# miniprinter_x_axis.net
KiCad netlist of a schematic drawn in EAGLE
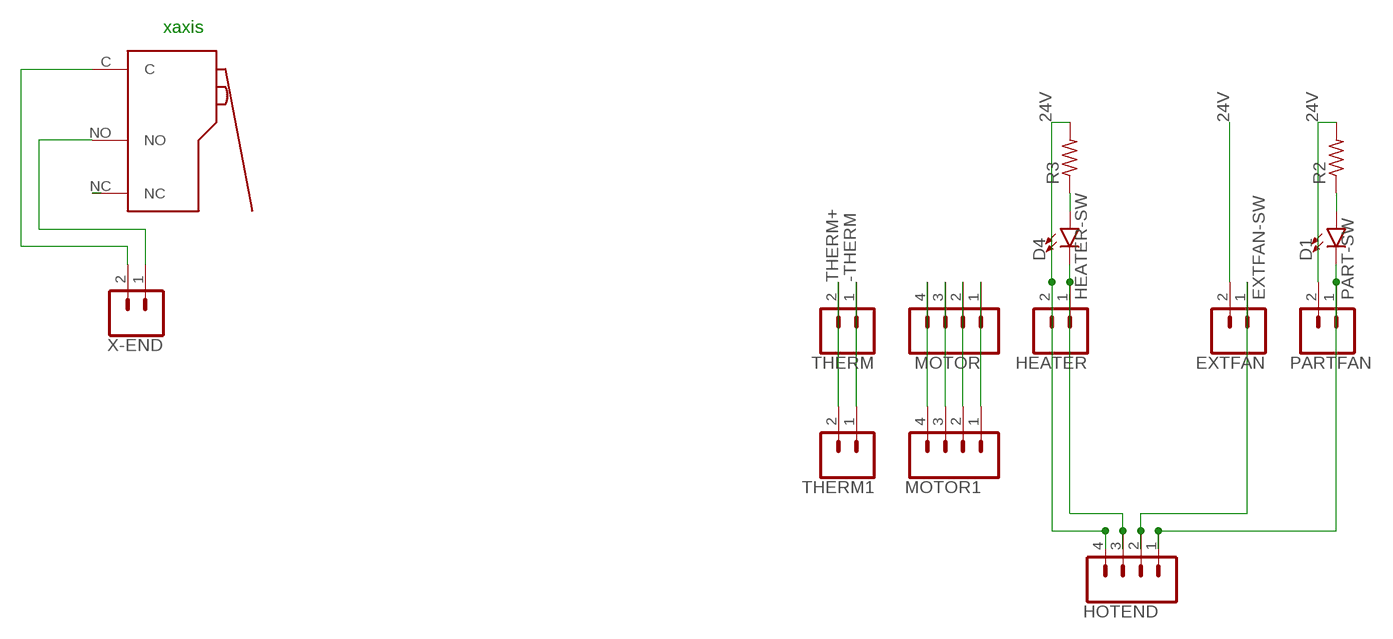
[diagram p0: schematic, sheet 1]

(export (version "E")
  (design (tool "Eeschema 10.0.6"))
  (components
    (comp (ref "D1")
      (value "LED-FKIT-1206")
      (footprint "eagle-import:FKIT-LED-1206")
      (libsource (lib "eagle-import") (part "LED-FKIT-1206"))
    )
    (comp (ref "D4")
      (value "LED-FKIT-1206")
      (footprint "eagle-import:FKIT-LED-1206")
      (libsource (lib "eagle-import") (part "LED-FKIT-1206"))
    )
    (comp (ref "EXTFAN")
      (value "CONN_023.5MM_LOCK")
      (footprint "eagle-import:SCREWTERMINAL-3.5MM-2_LOCK")
      (libsource (lib "eagle-import") (part "CONN_023.5MM_LOCK"))
    )
    (comp (ref "HEATER")
      (value "CONN_023.5MM_LOCK")
      (footprint "eagle-import:SCREWTERMINAL-3.5MM-2_LOCK")
      (libsource (lib "eagle-import") (part "CONN_023.5MM_LOCK"))
    )
    (comp (ref "HOTEND")
      (value "CONN_04SCREW_LOCK")
      (footprint "eagle-import:SCREWTERMINAL-3.5MM-4_LOCK")
      (libsource (lib "eagle-import") (part "CONN_04SCREW_LOCK"))
    )
    (comp (ref "MOTOR")
      (value "CONN_04SCREW_LOCK")
      (footprint "eagle-import:SCREWTERMINAL-3.5MM-4_LOCK")
      (libsource (lib "eagle-import") (part "CONN_04SCREW_LOCK"))
    )
    (comp (ref "MOTOR1")
      (value "CONN_04SCREW_LOCK")
      (footprint "eagle-import:SCREWTERMINAL-3.5MM-4_LOCK")
      (libsource (lib "eagle-import") (part "CONN_04SCREW_LOCK"))
    )
    (comp (ref "PARTFAN")
      (value "CONN_023.5MM_LOCK")
      (footprint "eagle-import:SCREWTERMINAL-3.5MM-2_LOCK")
      (libsource (lib "eagle-import") (part "CONN_023.5MM_LOCK"))
    )
    (comp (ref "R2")
      (value "R-US_R1206")
      (footprint "eagle-import:R1206")
      (libsource (lib "eagle-import") (part "R-US_R1206"))
    )
    (comp (ref "R3")
      (value "R-US_R1206")
      (footprint "eagle-import:R1206")
      (libsource (lib "eagle-import") (part "R-US_R1206"))
    )
    (comp (ref "THERM")
      (value "CONN_023.5MM_LOCK")
      (footprint "eagle-import:SCREWTERMINAL-3.5MM-2_LOCK")
      (libsource (lib "eagle-import") (part "CONN_023.5MM_LOCK"))
    )
    (comp (ref "THERM1")
      (value "CONN_023.5MM_LOCK")
      (footprint "eagle-import:SCREWTERMINAL-3.5MM-2_LOCK")
      (libsource (lib "eagle-import") (part "CONN_023.5MM_LOCK"))
    )
    (comp (ref "U$2")
      (value "Lever Microswitch Leftangle PCB mount, with Roller style lever, with a red roller")
      (footprint "eagle-import:LEVERMICROPCB-LEFTANGLE")
      (libsource (lib "eagle-import") (part "LEVERMICROPCBLEFTANGLE"))
    )
    (comp (ref "X-END")
      (value "CONN_023.5MM_LOCK")
      (footprint "eagle-import:SCREWTERMINAL-3.5MM-2_LOCK")
      (libsource (lib "eagle-import") (part "CONN_023.5MM_LOCK"))
    )
  )
  (nets
    (net (code "1") (name "/-THERM") (class "Default")
      (node (ref "THERM") (pin "1") (pinfunction "1_1") (pintype "passive"))
      (node (ref "THERM1") (pin "1") (pinfunction "1_1") (pintype "passive"))
    )
    (net (code "2") (name "/24V") (class "Default")
      (node (ref "EXTFAN") (pin "2") (pinfunction "2_2") (pintype "passive"))
      (node (ref "HEATER") (pin "2") (pinfunction "2_2") (pintype "passive"))
      (node (ref "HOTEND") (pin "4") (pinfunction "4_4") (pintype "passive"))
      (node (ref "PARTFAN") (pin "2") (pinfunction "2_2") (pintype "passive"))
      (node (ref "R2") (pin "2") (pinfunction "2_2") (pintype "passive"))
      (node (ref "R3") (pin "2") (pinfunction "2_2") (pintype "passive"))
    )
    (net (code "3") (name "/EXTFAN-SW") (class "Default")
      (node (ref "EXTFAN") (pin "1") (pinfunction "1_1") (pintype "passive"))
      (node (ref "HOTEND") (pin "2") (pinfunction "2_2") (pintype "passive"))
    )
    (net (code "4") (name "/HEATER-SW") (class "Default")
      (node (ref "D4") (pin "C") (pinfunction "C_C") (pintype "passive"))
      (node (ref "HEATER") (pin "1") (pinfunction "1_1") (pintype "passive"))
      (node (ref "HOTEND") (pin "3") (pinfunction "3_3") (pintype "passive"))
    )
    (net (code "5") (name "/PART-SW") (class "Default")
      (node (ref "D1") (pin "C") (pinfunction "C_C") (pintype "passive"))
      (node (ref "HOTEND") (pin "1") (pinfunction "1_1") (pintype "passive"))
      (node (ref "PARTFAN") (pin "1") (pinfunction "1_1") (pintype "passive"))
    )
    (net (code "6") (name "/THERM+") (class "Default")
      (node (ref "THERM") (pin "2") (pinfunction "2_2") (pintype "passive"))
      (node (ref "THERM1") (pin "2") (pinfunction "2_2") (pintype "passive"))
    )
    (net (code "7") (name "Net-(D1-PadA)") (class "Default")
      (node (ref "D1") (pin "A") (pinfunction "A_A") (pintype "passive"))
      (node (ref "R2") (pin "1") (pinfunction "1_1") (pintype "passive"))
    )
    (net (code "8") (name "Net-(D4-PadA)") (class "Default")
      (node (ref "D4") (pin "A") (pinfunction "A_A") (pintype "passive"))
      (node (ref "R3") (pin "1") (pinfunction "1_1") (pintype "passive"))
    )
    (net (code "9") (name "Net-(MOTOR-Pad1)") (class "Default")
      (node (ref "MOTOR") (pin "1") (pinfunction "1_1") (pintype "passive"))
      (node (ref "MOTOR1") (pin "1") (pinfunction "1_1") (pintype "passive"))
    )
    (net (code "10") (name "Net-(MOTOR-Pad2)") (class "Default")
      (node (ref "MOTOR") (pin "2") (pinfunction "2_2") (pintype "passive"))
      (node (ref "MOTOR1") (pin "2") (pinfunction "2_2") (pintype "passive"))
    )
    (net (code "11") (name "Net-(MOTOR-Pad3)") (class "Default")
      (node (ref "MOTOR") (pin "3") (pinfunction "3_3") (pintype "passive"))
      (node (ref "MOTOR1") (pin "3") (pinfunction "3_3") (pintype "passive"))
    )
    (net (code "12") (name "Net-(MOTOR-Pad4)") (class "Default")
      (node (ref "MOTOR") (pin "4") (pinfunction "4_4") (pintype "passive"))
      (node (ref "MOTOR1") (pin "4") (pinfunction "4_4") (pintype "passive"))
    )
    (net (code "13") (name "Net-(U$2-PadC)") (class "Default")
      (node (ref "U$2") (pin "C") (pinfunction "C_C") (pintype "bidirectional"))
      (node (ref "X-END") (pin "2") (pinfunction "2_2") (pintype "passive"))
    )
    (net (code "14") (name "Net-(U$2-PadNO)") (class "Default")
      (node (ref "U$2") (pin "NO") (pinfunction "NO_NO") (pintype "bidirectional"))
      (node (ref "X-END") (pin "1") (pinfunction "1_1") (pintype "passive"))
    )
    (net (code "15") (name "unconnected-(U$2-PadNC)") (class "Default")
      (node (ref "U$2") (pin "NC") (pinfunction "NC_NC") (pintype "bidirectional"))
    )
  )
)
